# CT100-array.net
KiCad netlist of a schematic drawn in Altium Designer
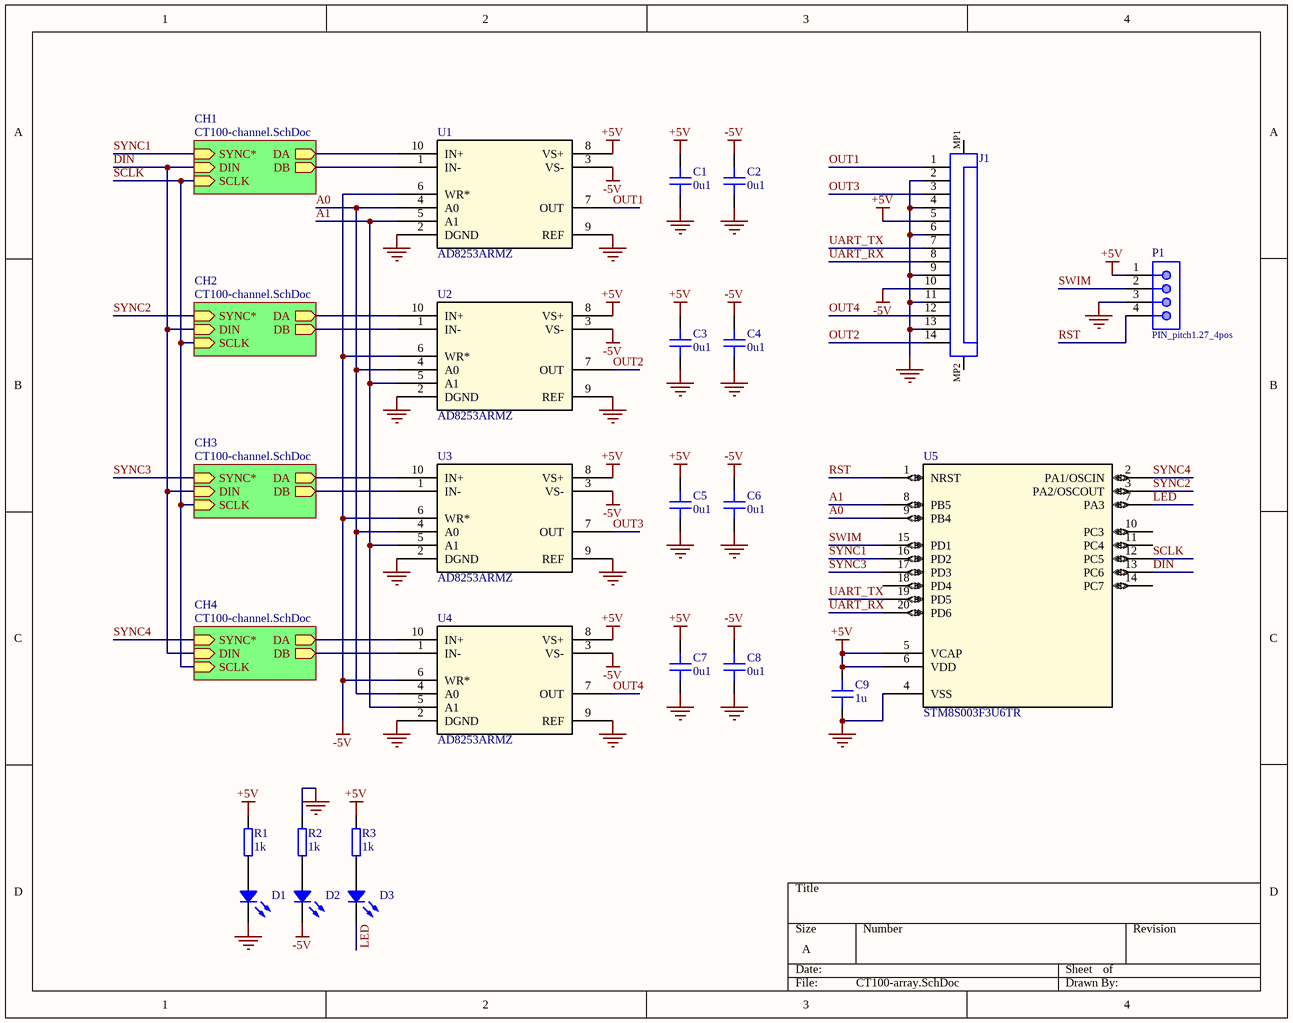
[diagram p0: CT100-array.SchDoc]

(export (version "E")
  (design (tool "Eeschema 10.0.6"))
  (components
    (comp (ref "C1")
      (value "0u1")
      (footprint "CAP_0402")
      (description "Capacitor SMD 0402")
      (fields (field (name "VOLTAGE") "50V"))
      (libsource (lib "symbols") (part "CAP_0402"))
    )
    (comp (ref "C2")
      (value "0u1")
      (footprint "CAP_0402")
      (description "Capacitor SMD 0402")
      (fields (field (name "VOLTAGE") "50V"))
      (libsource (lib "symbols") (part "CAP_0402"))
    )
    (comp (ref "C3")
      (value "0u1")
      (footprint "CAP_0402")
      (description "Capacitor SMD 0402")
      (fields (field (name "VOLTAGE") "50V"))
      (libsource (lib "symbols") (part "CAP_0402"))
    )
    (comp (ref "C4")
      (value "0u1")
      (footprint "CAP_0402")
      (description "Capacitor SMD 0402")
      (fields (field (name "VOLTAGE") "50V"))
      (libsource (lib "symbols") (part "CAP_0402"))
    )
    (comp (ref "C5")
      (value "0u1")
      (footprint "CAP_0402")
      (description "Capacitor SMD 0402")
      (fields (field (name "VOLTAGE") "50V"))
      (libsource (lib "symbols") (part "CAP_0402"))
    )
    (comp (ref "C6")
      (value "0u1")
      (footprint "CAP_0402")
      (description "Capacitor SMD 0402")
      (fields (field (name "VOLTAGE") "50V"))
      (libsource (lib "symbols") (part "CAP_0402"))
    )
    (comp (ref "C7")
      (value "0u1")
      (footprint "CAP_0402")
      (description "Capacitor SMD 0402")
      (fields (field (name "VOLTAGE") "50V"))
      (libsource (lib "symbols") (part "CAP_0402"))
    )
    (comp (ref "C8")
      (value "0u1")
      (footprint "CAP_0402")
      (description "Capacitor SMD 0402")
      (fields (field (name "VOLTAGE") "50V"))
      (libsource (lib "symbols") (part "CAP_0402"))
    )
    (comp (ref "C9")
      (value "1u")
      (footprint "CAP_0402")
      (description "Capacitor SMD 0402")
      (fields (field (name "VOLTAGE") "50V"))
      (libsource (lib "symbols") (part "CAP_0402"))
    )
    (comp (ref "D1")
      (value "LED_0402")
      (footprint "LED_0402")
      (description "LED SMD 0402")
      (libsource (lib "symbols") (part "LED_0402"))
    )
    (comp (ref "D2")
      (value "LED_0402")
      (footprint "LED_0402")
      (description "LED SMD 0402")
      (libsource (lib "symbols") (part "LED_0402"))
    )
    (comp (ref "D3")
      (value "LED_0402")
      (footprint "LED_0402")
      (description "LED SMD 0402")
      (libsource (lib "symbols") (part "LED_0402"))
    )
    (comp (ref "J1")
      (value "FPC_pitch1_14pos")
      (footprint "FPC_pitch1_14pos")
      (description "14 Position 1 mm FFC & FPC Connectors")
      (libsource (lib "symbols") (part "FPC_pitch1_14pos"))
    )
    (comp (ref "P1")
      (value "PIN_pitch1.27_4pos")
      (footprint "PIN_pitch1.27_4pos")
      (libsource (lib "symbols") (part "PIN_pitch1.27_4pos"))
    )
    (comp (ref "R1")
      (value "1k")
      (footprint "RES_0402")
      (description "Resistor SMD 0402")
      (libsource (lib "symbols") (part "RES_0402"))
    )
    (comp (ref "R2")
      (value "1k")
      (footprint "RES_0402")
      (description "Resistor SMD 0402")
      (libsource (lib "symbols") (part "RES_0402"))
    )
    (comp (ref "R3")
      (value "1k")
      (footprint "RES_0402")
      (description "Resistor SMD 0402")
      (libsource (lib "symbols") (part "RES_0402"))
    )
    (comp (ref "U1")
      (value "AD8253ARMZ")
      (footprint "RM_10_ADI")
      (description "No Description Available")
      (fields (field (name "COPYRIGHT") "Copyright (C) 2023 Ultra Librarian. All rights reserved."))
      (libsource (lib "symbols") (part "AD8253ARMZ"))
    )
    (comp (ref "U2")
      (value "AD8253ARMZ")
      (footprint "RM_10_ADI")
      (description "No Description Available")
      (fields (field (name "COPYRIGHT") "Copyright (C) 2023 Ultra Librarian. All rights reserved."))
      (libsource (lib "symbols") (part "AD8253ARMZ"))
    )
    (comp (ref "U3")
      (value "AD8253ARMZ")
      (footprint "RM_10_ADI")
      (description "No Description Available")
      (fields (field (name "COPYRIGHT") "Copyright (C) 2023 Ultra Librarian. All rights reserved."))
      (libsource (lib "symbols") (part "AD8253ARMZ"))
    )
    (comp (ref "U4")
      (value "AD8253ARMZ")
      (footprint "RM_10_ADI")
      (description "No Description Available")
      (fields (field (name "COPYRIGHT") "Copyright (C) 2023 Ultra Librarian. All rights reserved."))
      (libsource (lib "symbols") (part "AD8253ARMZ"))
    )
    (comp (ref "U5")
      (value "STM8S003F3U6TR")
      (footprint "UFQFPN20_3x3x0p6")
      (description "No Description Available")
      (fields (field (name "COPYRIGHT") "Copyright (C) 2023 Ultra Librarian. All rights reserved."))
      (libsource (lib "symbols") (part "STM8S003F3U6TR"))
    )
  )
  (nets
    (net (code "1") (name "+5V") (class "Default")
      (node (ref "C1") (pin "1") (pinfunction "1_1") (pintype "passive"))
      (node (ref "C3") (pin "1") (pinfunction "1_1") (pintype "passive"))
      (node (ref "C5") (pin "1") (pinfunction "1_1") (pintype "passive"))
      (node (ref "C7") (pin "1") (pinfunction "1_1") (pintype "passive"))
      (node (ref "C9") (pin "1") (pinfunction "1_1") (pintype "passive"))
      (node (ref "J1") (pin "5") (pinfunction "5_5") (pintype "passive"))
      (node (ref "P1") (pin "1") (pinfunction "1_1") (pintype "passive"))
      (node (ref "R1") (pin "2") (pinfunction "2_2") (pintype "passive"))
      (node (ref "R3") (pin "2") (pinfunction "2_2") (pintype "passive"))
      (node (ref "U1") (pin "8") (pinfunction "VS+_8") (pintype "power_in"))
      (node (ref "U2") (pin "8") (pinfunction "VS+_8") (pintype "power_in"))
      (node (ref "U3") (pin "8") (pinfunction "VS+_8") (pintype "power_in"))
      (node (ref "U4") (pin "8") (pinfunction "VS+_8") (pintype "power_in"))
      (node (ref "U5") (pin "5") (pinfunction "VCAP_5") (pintype "power_in"))
      (node (ref "U5") (pin "6") (pinfunction "VDD_6") (pintype "power_in"))
    )
    (net (code "2") (name "-5V") (class "Default")
      (node (ref "C2") (pin "1") (pinfunction "1_1") (pintype "passive"))
      (node (ref "C4") (pin "1") (pinfunction "1_1") (pintype "passive"))
      (node (ref "C6") (pin "1") (pinfunction "1_1") (pintype "passive"))
      (node (ref "C8") (pin "1") (pinfunction "1_1") (pintype "passive"))
      (node (ref "D2") (pin "2") (pinfunction "2_2") (pintype "passive"))
      (node (ref "J1") (pin "10") (pinfunction "10_10") (pintype "passive"))
      (node (ref "U1") (pin "3") (pinfunction "VS-_3") (pintype "power_in"))
      (node (ref "U1") (pin "6") (pinfunction "WR*_6") (pintype "passive"))
      (node (ref "U2") (pin "3") (pinfunction "VS-_3") (pintype "power_in"))
      (node (ref "U2") (pin "6") (pinfunction "WR*_6") (pintype "passive"))
      (node (ref "U3") (pin "3") (pinfunction "VS-_3") (pintype "power_in"))
      (node (ref "U3") (pin "6") (pinfunction "WR*_6") (pintype "passive"))
      (node (ref "U4") (pin "3") (pinfunction "VS-_3") (pintype "power_in"))
      (node (ref "U4") (pin "6") (pinfunction "WR*_6") (pintype "passive"))
    )
    (net (code "3") (name "/A0") (class "Default")
      (node (ref "U1") (pin "4") (pinfunction "A0_4") (pintype "passive"))
      (node (ref "U2") (pin "4") (pinfunction "A0_4") (pintype "passive"))
      (node (ref "U3") (pin "4") (pinfunction "A0_4") (pintype "passive"))
      (node (ref "U4") (pin "4") (pinfunction "A0_4") (pintype "passive"))
      (node (ref "U5") (pin "9") (pinfunction "PB4_9") (pintype "bidirectional"))
    )
    (net (code "4") (name "/A1") (class "Default")
      (node (ref "U1") (pin "5") (pinfunction "A1_5") (pintype "passive"))
      (node (ref "U2") (pin "5") (pinfunction "A1_5") (pintype "passive"))
      (node (ref "U3") (pin "5") (pinfunction "A1_5") (pintype "passive"))
      (node (ref "U4") (pin "5") (pinfunction "A1_5") (pintype "passive"))
      (node (ref "U5") (pin "8") (pinfunction "PB5_8") (pintype "bidirectional"))
    )
    (net (code "5") (name "/DA") (class "Default")
      (node (ref "U4") (pin "10") (pinfunction "IN+_10") (pintype "passive"))
    )
    (net (code "6") (name "/DA_1") (class "Default")
      (node (ref "U1") (pin "10") (pinfunction "IN+_10") (pintype "passive"))
    )
    (net (code "7") (name "/DA_2") (class "Default")
      (node (ref "U2") (pin "10") (pinfunction "IN+_10") (pintype "passive"))
    )
    (net (code "8") (name "/DA_3") (class "Default")
      (node (ref "U3") (pin "10") (pinfunction "IN+_10") (pintype "passive"))
    )
    (net (code "9") (name "/DB") (class "Default")
      (node (ref "U4") (pin "1") (pinfunction "IN-_1") (pintype "passive"))
    )
    (net (code "10") (name "/DB_1") (class "Default")
      (node (ref "U1") (pin "1") (pinfunction "IN-_1") (pintype "passive"))
    )
    (net (code "11") (name "/DB_2") (class "Default")
      (node (ref "U2") (pin "1") (pinfunction "IN-_1") (pintype "passive"))
    )
    (net (code "12") (name "/DB_3") (class "Default")
      (node (ref "U3") (pin "1") (pinfunction "IN-_1") (pintype "passive"))
    )
    (net (code "13") (name "/DIN") (class "Default")
      (node (ref "U5") (pin "13") (pinfunction "PC6_13") (pintype "bidirectional"))
    )
    (net (code "14") (name "/LED") (class "Default")
      (node (ref "D3") (pin "2") (pinfunction "2_2") (pintype "passive"))
      (node (ref "U5") (pin "7") (pinfunction "PA3_7") (pintype "bidirectional"))
    )
    (net (code "15") (name "/OUT1") (class "Default")
      (node (ref "J1") (pin "1") (pinfunction "1_1") (pintype "passive"))
      (node (ref "U1") (pin "7") (pinfunction "OUT_7") (pintype "passive"))
    )
    (net (code "16") (name "/OUT2") (class "Default")
      (node (ref "J1") (pin "14") (pinfunction "14_14") (pintype "passive"))
      (node (ref "U2") (pin "7") (pinfunction "OUT_7") (pintype "passive"))
    )
    (net (code "17") (name "/OUT3") (class "Default")
      (node (ref "J1") (pin "3") (pinfunction "3_3") (pintype "passive"))
      (node (ref "U3") (pin "7") (pinfunction "OUT_7") (pintype "passive"))
    )
    (net (code "18") (name "/OUT4") (class "Default")
      (node (ref "J1") (pin "12") (pinfunction "12_12") (pintype "passive"))
      (node (ref "U4") (pin "7") (pinfunction "OUT_7") (pintype "passive"))
    )
    (net (code "19") (name "/RST") (class "Default")
      (node (ref "P1") (pin "4") (pinfunction "4_4") (pintype "passive"))
      (node (ref "U5") (pin "1") (pinfunction "NRST_1") (pintype "bidirectional"))
    )
    (net (code "20") (name "/SCLK") (class "Default")
      (node (ref "U5") (pin "12") (pinfunction "PC5_12") (pintype "bidirectional"))
    )
    (net (code "21") (name "/SWIM") (class "Default")
      (node (ref "P1") (pin "2") (pinfunction "2_2") (pintype "passive"))
      (node (ref "U5") (pin "15") (pinfunction "PD1_15") (pintype "bidirectional"))
    )
    (net (code "22") (name "/SYNC1") (class "Default")
      (node (ref "U5") (pin "16") (pinfunction "PD2_16") (pintype "bidirectional"))
    )
    (net (code "23") (name "/SYNC2") (class "Default")
      (node (ref "U5") (pin "3") (pinfunction "PA2/OSCOUT_3") (pintype "bidirectional"))
    )
    (net (code "24") (name "/SYNC3") (class "Default")
      (node (ref "U5") (pin "17") (pinfunction "PD3_17") (pintype "bidirectional"))
    )
    (net (code "25") (name "/SYNC4") (class "Default")
      (node (ref "U5") (pin "2") (pinfunction "PA1/OSCIN_2") (pintype "bidirectional"))
    )
    (net (code "26") (name "/UART_RX") (class "Default")
      (node (ref "J1") (pin "8") (pinfunction "8_8") (pintype "passive"))
      (node (ref "U5") (pin "20") (pinfunction "PD6_20") (pintype "bidirectional"))
    )
    (net (code "27") (name "/UART_TX") (class "Default")
      (node (ref "J1") (pin "7") (pinfunction "7_7") (pintype "passive"))
      (node (ref "U5") (pin "19") (pinfunction "PD5_19") (pintype "bidirectional"))
    )
    (net (code "28") (name "GND") (class "Default")
      (node (ref "C1") (pin "2") (pinfunction "2_2") (pintype "passive"))
      (node (ref "C2") (pin "2") (pinfunction "2_2") (pintype "passive"))
      (node (ref "C3") (pin "2") (pinfunction "2_2") (pintype "passive"))
      (node (ref "C4") (pin "2") (pinfunction "2_2") (pintype "passive"))
      (node (ref "C5") (pin "2") (pinfunction "2_2") (pintype "passive"))
      (node (ref "C6") (pin "2") (pinfunction "2_2") (pintype "passive"))
      (node (ref "C7") (pin "2") (pinfunction "2_2") (pintype "passive"))
      (node (ref "C8") (pin "2") (pinfunction "2_2") (pintype "passive"))
      (node (ref "C9") (pin "2") (pinfunction "2_2") (pintype "passive"))
      (node (ref "D1") (pin "2") (pinfunction "2_2") (pintype "passive"))
      (node (ref "J1") (pin "11") (pinfunction "11_11") (pintype "passive"))
      (node (ref "J1") (pin "13") (pinfunction "13_13") (pintype "passive"))
      (node (ref "J1") (pin "2") (pinfunction "2_2") (pintype "passive"))
      (node (ref "J1") (pin "4") (pinfunction "4_4") (pintype "passive"))
      (node (ref "J1") (pin "6") (pinfunction "6_6") (pintype "passive"))
      (node (ref "J1") (pin "9") (pinfunction "9_9") (pintype "passive"))
      (node (ref "P1") (pin "3") (pinfunction "3_3") (pintype "passive"))
      (node (ref "R2") (pin "2") (pinfunction "2_2") (pintype "passive"))
      (node (ref "U1") (pin "2") (pinfunction "DGND_2") (pintype "passive"))
      (node (ref "U1") (pin "9") (pinfunction "REF_9") (pintype "passive"))
      (node (ref "U2") (pin "2") (pinfunction "DGND_2") (pintype "passive"))
      (node (ref "U2") (pin "9") (pinfunction "REF_9") (pintype "passive"))
      (node (ref "U3") (pin "2") (pinfunction "DGND_2") (pintype "passive"))
      (node (ref "U3") (pin "9") (pinfunction "REF_9") (pintype "passive"))
      (node (ref "U4") (pin "2") (pinfunction "DGND_2") (pintype "passive"))
      (node (ref "U4") (pin "9") (pinfunction "REF_9") (pintype "passive"))
      (node (ref "U5") (pin "4") (pinfunction "VSS_4") (pintype "power_in"))
    )
    (net (code "29") (name "Net-(D1-Pad1)") (class "Default")
      (node (ref "D1") (pin "1") (pinfunction "1_1") (pintype "passive"))
      (node (ref "R1") (pin "1") (pinfunction "1_1") (pintype "passive"))
    )
    (net (code "30") (name "Net-(D2-Pad1)") (class "Default")
      (node (ref "D2") (pin "1") (pinfunction "1_1") (pintype "passive"))
      (node (ref "R2") (pin "1") (pinfunction "1_1") (pintype "passive"))
    )
    (net (code "31") (name "Net-(D3-Pad1)") (class "Default")
      (node (ref "D3") (pin "1") (pinfunction "1_1") (pintype "passive"))
      (node (ref "R3") (pin "1") (pinfunction "1_1") (pintype "passive"))
    )
    (net (code "32") (name "unconnected-(J1-PadMP1)") (class "Default")
      (node (ref "J1") (pin "MP1") (pinfunction "MP1_MP1") (pintype "passive"))
    )
    (net (code "33") (name "unconnected-(J1-PadMP2)") (class "Default")
      (node (ref "J1") (pin "MP2") (pinfunction "MP2_MP2") (pintype "passive"))
    )
    (net (code "34") (name "unconnected-(U5-PC3-Pad10)") (class "Default")
      (node (ref "U5") (pin "10") (pinfunction "PC3_10") (pintype "bidirectional"))
    )
    (net (code "35") (name "unconnected-(U5-PC4-Pad11)") (class "Default")
      (node (ref "U5") (pin "11") (pinfunction "PC4_11") (pintype "bidirectional"))
    )
    (net (code "36") (name "unconnected-(U5-PC7-Pad14)") (class "Default")
      (node (ref "U5") (pin "14") (pinfunction "PC7_14") (pintype "bidirectional"))
    )
    (net (code "37") (name "unconnected-(U5-PD4-Pad18)") (class "Default")
      (node (ref "U5") (pin "18") (pinfunction "PD4_18") (pintype "bidirectional"))
    )
  )
)
